# wpf-badge.net
KiCad netlist of a schematic drawn in EAGLE
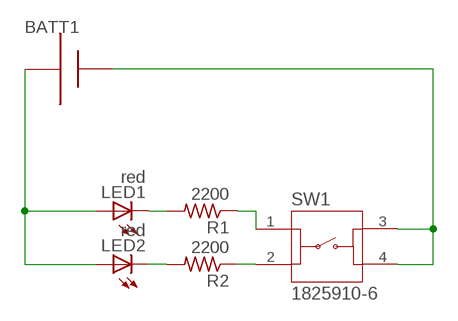
[diagram p0: schematic, sheet 1]

(export (version "E")
  (design (tool "Eeschema 10.0.6"))
  (components
    (comp (ref "BATT1")
      (value "AAA")
      (footprint "eagle-import:12BH412")
      (libsource (lib "eagle-import") (part "AAA"))
    )
    (comp (ref "LED1")
      (value "red")
      (footprint "eagle-import:LED3MM")
      (libsource (lib "eagle-import") (part "LED3MM"))
    )
    (comp (ref "LED2")
      (value "red")
      (footprint "eagle-import:LED3MM")
      (libsource (lib "eagle-import") (part "LED3MM"))
    )
    (comp (ref "R1")
      (value "2200")
      (footprint "eagle-import:0204_7")
      (libsource (lib "eagle-import") (part "R-US_0204/7"))
    )
    (comp (ref "R2")
      (value "2200")
      (footprint "eagle-import:0204_7")
      (libsource (lib "eagle-import") (part "R-US_0204/7"))
    )
    (comp (ref "SW1")
      (value "1825910-6")
      (footprint "eagle-import:SW_1825910-6-4")
      (fields (field (name "DIGI-KEY_PART_NUMBER") "450-1650-ND") (field (name "MF") "TE Connectivity"))
      (libsource (lib "eagle-import") (part "1825910-6"))
    )
  )
  (nets
    (net (code "1") (name "Net-(BATT1-Pad+)") (class "Default")
      (node (ref "BATT1") (pin "+") (pinfunction "+_+") (pintype "bidirectional"))
      (node (ref "SW1") (pin "3") (pinfunction "3_3") (pintype "passive"))
      (node (ref "SW1") (pin "4") (pinfunction "4_4") (pintype "passive"))
    )
    (net (code "2") (name "Net-(BATT1-Pad-)") (class "Default")
      (node (ref "BATT1") (pin "-") (pinfunction "-_-") (pintype "bidirectional"))
      (node (ref "LED1") (pin "A") (pinfunction "A_A") (pintype "passive"))
      (node (ref "LED2") (pin "A") (pinfunction "A_A") (pintype "passive"))
    )
    (net (code "3") (name "Net-(LED1-C)") (class "Default")
      (node (ref "LED1") (pin "K") (pinfunction "C_K") (pintype "passive"))
      (node (ref "R1") (pin "2") (pinfunction "2_2") (pintype "passive"))
    )
    (net (code "4") (name "Net-(LED2-C)") (class "Default")
      (node (ref "LED2") (pin "K") (pinfunction "C_K") (pintype "passive"))
      (node (ref "R2") (pin "2") (pinfunction "2_2") (pintype "passive"))
    )
    (net (code "5") (name "Net-(R1-Pad1)") (class "Default")
      (node (ref "R1") (pin "1") (pinfunction "1_1") (pintype "passive"))
      (node (ref "SW1") (pin "1") (pinfunction "1_1") (pintype "passive"))
    )
    (net (code "6") (name "Net-(R2-Pad1)") (class "Default")
      (node (ref "R2") (pin "1") (pinfunction "1_1") (pintype "passive"))
      (node (ref "SW1") (pin "2") (pinfunction "2_2") (pintype "passive"))
    )
  )
)
